# BMS_FIltering.net
KiCad netlist of a schematic drawn in Altium Designer
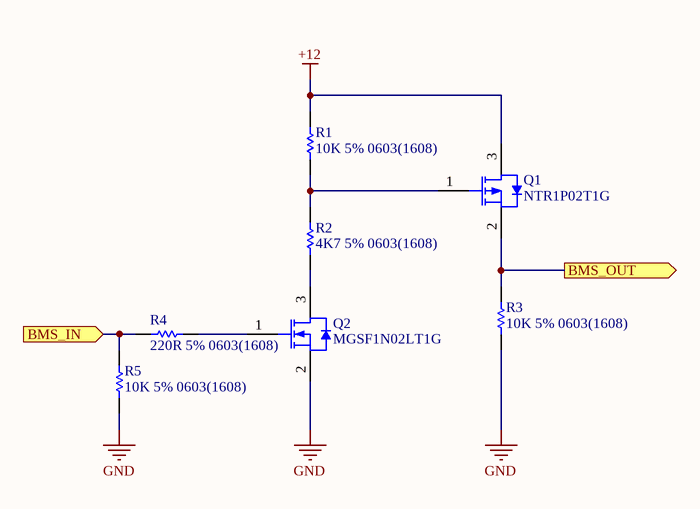
[diagram p0: BMS_FIltering.SchDoc]

(export (version "E")
  (design (tool "Eeschema 10.0.6"))
  (components
    (comp (ref "Q1")
      (value "NTR1P02T1G")
      (footprint "ONSC-SOT-23-3-318-08_V")
      (description "Power MOSFET, -20 V, -1 A, P-Channel, 3-Pin SOT-23, Pb-Free, Tape and Reel")
      (fields (field (name "MANUFACTURER") "On Semiconductor"))
      (libsource (lib "Altium Content Vault") (part "ONSC-PMOS-G1S2D3-3_D"))
    )
    (comp (ref "Q2")
      (value "MGSF1N02LT1G")
      (footprint "ONSC-SOT-23-3-318-08_V")
      (description "Power MOSFET, 750 mA, 20 V, N-Channel, 3-Pin SOT-23, Pb-Free, Tape and Reel")
      (fields (field (name "MANUFACTURER") "On Semiconductor"))
      (libsource (lib "Altium Content Vault") (part "ONSC-NMOS-G1S2D3-3"))
    )
    (comp (ref "R1")
      (value "10K 5% 0603(1608)")
      (footprint "RESC0603(1608)_N")
      (description "10K 0.1W 5% 0603 (1608 Metric)  SMD")
      (fields (field (name "TOLERANCE") "5 %") (field (name "POWER") "0.1 W"))
      (libsource (lib "Altium Content Vault") (part "RES"))
    )
    (comp (ref "R2")
      (value "4K7 5% 0603(1608)")
      (footprint "RESC0603(1608)_N")
      (description "4K7 0.1W 5% 0603 (1608 Metric)  SMD")
      (fields (field (name "TOLERANCE") "5 %") (field (name "POWER") "0.1 W"))
      (libsource (lib "Altium Content Vault") (part "RES"))
    )
    (comp (ref "R3")
      (value "10K 5% 0603(1608)")
      (footprint "RESC0603(1608)_N")
      (description "10K 0.1W 5% 0603 (1608 Metric)  SMD")
      (fields (field (name "TOLERANCE") "5 %") (field (name "POWER") "0.1 W"))
      (libsource (lib "Altium Content Vault") (part "RES"))
    )
    (comp (ref "R4")
      (value "220R 5% 0603(1608)")
      (footprint "RESC0603(1608)_M")
      (description "220R 0.1W 5% 0603 (1608 Metric)  SMD")
      (fields (field (name "POWER") "0.1 W") (field (name "TOLERANCE") "5 %"))
      (libsource (lib "Altium Content Vault") (part "RES"))
    )
    (comp (ref "R5")
      (value "10K 5% 0603(1608)")
      (footprint "RESC0603(1608)_N")
      (description "10K 0.1W 5% 0603 (1608 Metric)  SMD")
      (fields (field (name "TOLERANCE") "5 %") (field (name "POWER") "0.1 W"))
      (libsource (lib "Altium Content Vault") (part "RES"))
    )
  )
  (nets
    (net (code "1") (name "+12") (class "Default")
      (node (ref "Q1") (pin "3") (pinfunction "D_3") (pintype "passive"))
      (node (ref "R1") (pin "2") (pinfunction "2_2") (pintype "passive"))
    )
    (net (code "2") (name "/BMS_IN") (class "Default")
      (node (ref "R4") (pin "1") (pinfunction "1_1") (pintype "passive"))
      (node (ref "R5") (pin "2") (pinfunction "2_2") (pintype "passive"))
    )
    (net (code "3") (name "/BMS_OUT") (class "Default")
      (node (ref "Q1") (pin "2") (pinfunction "S_2") (pintype "passive"))
      (node (ref "R3") (pin "2") (pinfunction "2_2") (pintype "passive"))
    )
    (net (code "4") (name "GND") (class "Default")
      (node (ref "Q2") (pin "2") (pinfunction "S_2") (pintype "passive"))
      (node (ref "R3") (pin "1") (pinfunction "1_1") (pintype "passive"))
      (node (ref "R5") (pin "1") (pinfunction "1_1") (pintype "passive"))
    )
    (net (code "5") (name "Net-(Q1-G)") (class "Default")
      (node (ref "Q1") (pin "1") (pinfunction "G_1") (pintype "passive"))
      (node (ref "R1") (pin "1") (pinfunction "1_1") (pintype "passive"))
      (node (ref "R2") (pin "2") (pinfunction "2_2") (pintype "passive"))
    )
    (net (code "6") (name "Net-(Q2-D)") (class "Default")
      (node (ref "Q2") (pin "3") (pinfunction "D_3") (pintype "passive"))
      (node (ref "R2") (pin "1") (pinfunction "1_1") (pintype "passive"))
    )
    (net (code "7") (name "Net-(Q2-G)") (class "Default")
      (node (ref "Q2") (pin "1") (pinfunction "G_1") (pintype "passive"))
      (node (ref "R4") (pin "2") (pinfunction "2_2") (pintype "passive"))
    )
  )
)
